# 12_-WIFI_Module_WF60.net
KiCad netlist of a schematic drawn in Altium Designer
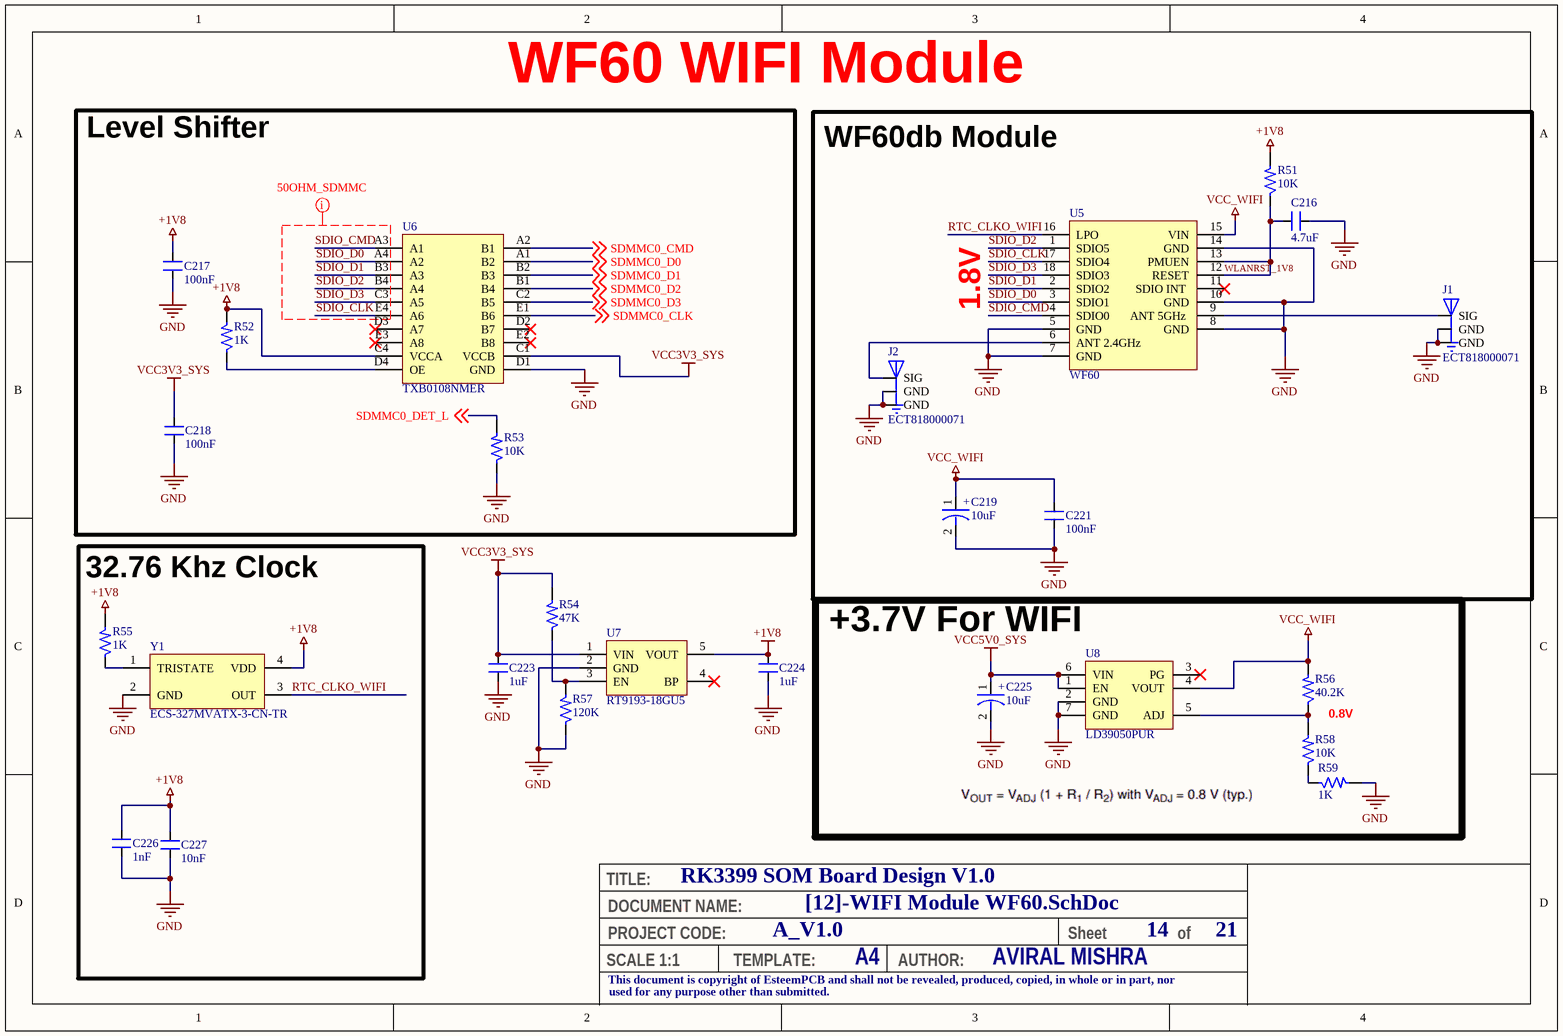
[diagram p0: [12]-WIFI Module WF60.SchDoc]

(export (version "E")
  (design (tool "Eeschema 10.0.6"))
  (components
    (comp (ref "C216")
      (value "4.7uF")
      (footprint "CAP_0402")
      (description "4.7µF ±10% 10V Ceramic Capacitor X5R 0402 (1005 Metric)")
      (fields
        (field (name "MANUFACTURER") "Samsung Electro-Mechanics")
        (field (name "MANUFACTURER PART NUMBER") "CL05A475KP5NRNC")
      )
      (libsource (lib "RK3399 _Module_Intlib") (part "CAP_4.7uF-10V-10%-0402"))
    )
    (comp (ref "C217")
      (value "100nF")
      (footprint "CAP_0402")
      (description "0.1µF ±10% 25V Ceramic Capacitor X7R 0402 (1005 Metric)")
      (fields
        (field (name "MANUFACTURER") "Walsin Technology Corporation")
        (field (name "MANUFACTURER PART NUMBER") "0402B104K250CT")
      )
      (libsource (lib "RK3399 _Module_Intlib") (part "CAP_100nF-25V-10%-0402"))
    )
    (comp (ref "C218")
      (value "100nF")
      (footprint "CAP_0402")
      (description "0.1µF ±10% 25V Ceramic Capacitor X7R 0402 (1005 Metric)")
      (fields
        (field (name "MANUFACTURER") "Walsin Technology Corporation")
        (field (name "MANUFACTURER PART NUMBER") "0402B104K250CT")
      )
      (libsource (lib "RK3399 _Module_Intlib") (part "CAP_100nF-25V-10%-0402"))
    )
    (comp (ref "C219")
      (value "10uF")
      (footprint "CAP-T_1206")
      (description "10µF Molded Tantalum Capacitors 16V 1206 (3216 Metric) 3Ohm")
      (fields
        (field (name "MANUFACTURER") "AVX Corporation")
        (field (name "MANUFACTURER PART NUMBER") "TAJA106K016SNJ")
      )
      (libsource (lib "RK3399 _Module_Intlib") (part "CAP-P_10uF-16V-10%-1206"))
    )
    (comp (ref "C221")
      (value "100nF")
      (footprint "CAP_0402")
      (description "0.1µF ±10% 25V Ceramic Capacitor X7R 0402 (1005 Metric)")
      (fields
        (field (name "MANUFACTURER") "Walsin Technology Corporation")
        (field (name "MANUFACTURER PART NUMBER") "0402B104K250CT")
      )
      (libsource (lib "RK3399 _Module_Intlib") (part "CAP_100nF-25V-10%-0402"))
    )
    (comp (ref "C223")
      (value "1uF")
      (footprint "CAP_0402")
      (description "1µF ±10% 16V Ceramic Capacitor X5R 0402 (1005 Metric)")
      (fields
        (field (name "MANUFACTURER") "Knowles Novacap")
        (field (name "MANUFACTURER PART NUMBER") "0402BW105K160YT")
      )
      (libsource (lib "RK3399 _Module_Schlib") (part "CAP_1uF-16V-10%-0402"))
    )
    (comp (ref "C224")
      (value "1uF")
      (footprint "CAP_0402")
      (description "1µF ±10% 16V Ceramic Capacitor X5R 0402 (1005 Metric)")
      (fields
        (field (name "MANUFACTURER") "Knowles Novacap")
        (field (name "MANUFACTURER PART NUMBER") "0402BW105K160YT")
      )
      (libsource (lib "RK3399 _Module_Schlib") (part "CAP_1uF-16V-10%-0402"))
    )
    (comp (ref "C225")
      (value "10uF")
      (footprint "CAP-T_1206")
      (description "10µF Molded Tantalum Capacitors 16V 1206 (3216 Metric) 3Ohm")
      (fields
        (field (name "MANUFACTURER") "AVX Corporation")
        (field (name "MANUFACTURER PART NUMBER") "TAJA106K016SNJ")
      )
      (libsource (lib "RK3399 _Module_Intlib") (part "CAP-P_10uF-16V-10%-1206"))
    )
    (comp (ref "C226")
      (value "1nF")
      (footprint "CAP_0402")
      (description "1000pF ±10% 16V Ceramic Capacitor X7R 0402 (1005 Metric)")
      (fields
        (field (name "MANUFACTURER") "Yageo")
        (field (name "MANUFACTURER PART NUMBER") "CC0402KRX7R7BB102")
      )
      (libsource (lib "RK3399 _Module_Intlib") (part "CAP_1nF-16V-10%-0402"))
    )
    (comp (ref "C227")
      (value "10nF")
      (footprint "CAP_0402")
      (description "10000pF ±10% 10V Ceramic Capacitor X7R 0402 (1005 Metric)")
      (fields
        (field (name "MANUFACTURER") "AVX Corporation")
        (field (name "MANUFACTURER PART NUMBER") "0402ZC103KAT2A")
      )
      (libsource (lib "RK3399 _Module_Intlib") (part "CAP_10nF-10V-10%-0402"))
    )
    (comp (ref "J1")
      (value "ECT818000071")
      (footprint "CON3_UFL_116_SMD_ST")
      (description "SMD RF Connectors/Coaxial Connectors RoHS")
      (fields (field (name "MANUFACTURER") "ECT"))
      (libsource (lib "RK3399 _Module_Intlib") (part "CON-PLG_3X1-ECT818000071-ST-SMD"))
    )
    (comp (ref "J2")
      (value "ECT818000071")
      (footprint "CON3_UFL_116_SMD_ST")
      (description "SMD RF Connectors/Coaxial Connectors RoHS")
      (fields (field (name "MANUFACTURER") "ECT"))
      (libsource (lib "RK3399 _Module_Intlib") (part "CON-PLG_3X1-ECT818000071-ST-SMD"))
    )
    (comp (ref "R51")
      (value "10K")
      (footprint "RES_0402")
      (description "10 kOhms ±1% 0.1W, 1/10W Chip Resistor 0402 (1005 Metric) Anti-Sulfur Thin Film")
      (fields
        (field (name "MANUFACTURER") "Vishay Beyschlag/Draloric/BC Components")
        (field (name "MANUFACTURER PART NUMBER") "MCS04020C1002FE000")
      )
      (libsource (lib "RK3399 _Module_Intlib") (part "RES_10K-0.1W-1%-0402"))
    )
    (comp (ref "R52")
      (value "1K")
      (footprint "RES_0402")
      (description "1 kOhms ±1% 0.1W, 1/10W Chip Resistor 0402 (1005 Metric) Anti-Sulfur Thin Film")
      (fields
        (field (name "MANUFACTURER") "Vishay Beyschlag/Draloric/BC Components")
        (field (name "MANUFACTURER PART NUMBER") "MCS04020C1001FE000")
      )
      (libsource (lib "RK3399 _Module_Intlib") (part "RES_1K-0.1W-1%-0402"))
    )
    (comp (ref "R53")
      (value "10K")
      (footprint "RES_0402")
      (description "10 kOhms ±1% 0.1W, 1/10W Chip Resistor 0402 (1005 Metric) Anti-Sulfur Thin Film")
      (fields
        (field (name "MANUFACTURER") "Vishay Beyschlag/Draloric/BC Components")
        (field (name "MANUFACTURER PART NUMBER") "MCS04020C1002FE000")
      )
      (libsource (lib "RK3399 _Module_Intlib") (part "RES_10K-0.1W-1%-0402"))
    )
    (comp (ref "R54")
      (value "47K")
      (footprint "RES_0402")
      (description "47 kOhms ±1% 0.1W, 1/10W Chip Resistor 0402 (1005 Metric) Automotive AEC-Q200 Thick Film")
      (fields
        (field (name "MANUFACTURER") "Panasonic Electronic Components")
        (field (name "MANUFACTURER PART NUMBER") "ERJ-2RKF4702X")
      )
      (libsource (lib "RK3399 _Module_Schlib") (part "RES_47K-0.1W-1%-0402"))
    )
    (comp (ref "R55")
      (value "1K")
      (footprint "RES_0402")
      (description "1 kOhms ±1% 0.1W, 1/10W Chip Resistor 0402 (1005 Metric) Anti-Sulfur Thin Film")
      (fields
        (field (name "MANUFACTURER") "Vishay Beyschlag/Draloric/BC Components")
        (field (name "MANUFACTURER PART NUMBER") "MCS04020C1001FE000")
      )
      (libsource (lib "RK3399 _Module_Intlib") (part "RES_1K-0.1W-1%-0402"))
    )
    (comp (ref "R56")
      (value "40.2K")
      (footprint "RES_0805")
      (description "40.2 kOhms ±1% 0.125W, 1/8W Chip Resistor 0805 (2012 Metric) Automotive AEC-Q200 Thick Film")
      (fields
        (field (name "MANUFACTURER") "TE Connectivity")
        (field (name "MANUFACTURER PART NUMBER") "RMCF0805FT40K2")
      )
      (libsource (lib "RK3399 _Module_Intlib") (part "RES_40.2K-0.125W-1%-0805"))
    )
    (comp (ref "R57")
      (value "120K")
      (footprint "RES_0402")
      (description "120 kOhms ±1% 0.1W, 1/10W Chip Resistor 0402 (1005 Metric) Anti-Sulfur Thin Film")
      (fields
        (field (name "MANUFACTURER") "Vishay Beyschlag/Draloric/BC Components")
        (field (name "MANUFACTURER PART NUMBER") "MCS04020C1203FE000")
      )
      (libsource (lib "RK3399 _Module_Schlib") (part "RES_120K-0.1W-1%-0402"))
    )
    (comp (ref "R58")
      (value "10K")
      (footprint "RES_0402")
      (description "10 kOhms ±1% 0.1W, 1/10W Chip Resistor 0402 (1005 Metric) Anti-Sulfur Thin Film")
      (fields
        (field (name "MANUFACTURER") "Vishay Beyschlag/Draloric/BC Components")
        (field (name "MANUFACTURER PART NUMBER") "MCS04020C1002FE000")
      )
      (libsource (lib "RK3399 _Module_Intlib") (part "RES_10K-0.1W-1%-0402"))
    )
    (comp (ref "R59")
      (value "1K")
      (footprint "RES_0402")
      (description "1 kOhms ±1% 0.1W, 1/10W Chip Resistor 0402 (1005 Metric) Anti-Sulfur Thin Film")
      (fields
        (field (name "MANUFACTURER") "Vishay Beyschlag/Draloric/BC Components")
        (field (name "MANUFACTURER PART NUMBER") "MCS04020C1001FE000")
      )
      (libsource (lib "RK3399 _Module_Intlib") (part "RES_1K-0.1W-1%-0402"))
    )
    (comp (ref "U5")
      (value "WF60")
      (footprint "MOD_WF60")
      (description "Amp’ed RF Tech presents the WF60 WiFi dual\r\nband module: 802.11abgn.")
      (fields (field (name "MANUFACTURER") "Amp’ed") (field (name "NYMBLE PART NUMBER") "1EA-AA-0568"))
      (libsource (lib "RK3399 _Module_Intlib") (part "MOD_WF60-SMD"))
    )
    (comp (ref "U6")
      (value "TXB0108NMER")
      (footprint "NFBGA_31.4_125.9X102.36")
      (fields (field (name "MANUFACTURER") "Texas Instruments"))
      (libsource (lib "RK3399 _Module_Intlib") (part "IC_TXB0108NMER"))
    )
    (comp (ref "U7")
      (value "RT9193-18GU5")
      (footprint "SC70-5")
      (description "Linear Voltage Regulator IC 1 Output 300mA SC-70-5")
      (fields (field (name "MANUFACTURER") "Richtek USA Inc."))
      (libsource (lib "RK3399 _Module_Schlib") (part "REG_1.8V-300mA-5.5V-SC70-5"))
    )
    (comp (ref "U8")
      (value "LD39050PUR")
      (footprint "DFN-6_37.4_165_33X15_SMD")
      (description "Adjustable 5.5V 0.8V 500mA DFN-6 Linear Voltage Regulators RoHS")
      (fields
        (field (name "MANUFACTURER") "STMicroelectronics")
        (field (name "NYMBLE PART NUMBER") "1EA-AA-0572")
      )
      (libsource (lib "RK3399 _Module_Intlib") (part "REG_5.5V-0~5.1V-0.5A-2.55W-DFN-6"))
    )
    (comp (ref "Y1")
      (value "ECS-327MVATX-3-CN-TR")
      (footprint "XTAL_57_35X31_SMD")
      (description "32.768kHz XO (Standard) CMOS Oscillator 1.6V ~ 3.6V Enable/Disable 4-SMD, No Lead")
      (fields (field (name "MANUFACTURER") "ECS INC") (field (name "NYMBLE PART NUMBER") "1EA-AA-0561"))
      (libsource (lib "RK3399 _Module_Intlib") (part "XTAL_ECS-327MVATX-2-CN-TR"))
    )
  )
  (nets
    (net (code "1") (name "+1V8") (class "Default")
      (node (ref "C217") (pin "2") (pinfunction "2_2") (pintype "passive"))
      (node (ref "C224") (pin "2") (pinfunction "2_2") (pintype "passive"))
      (node (ref "C226") (pin "2") (pinfunction "2_2") (pintype "passive"))
      (node (ref "C227") (pin "2") (pinfunction "2_2") (pintype "passive"))
      (node (ref "R51") (pin "2") (pinfunction "2_2") (pintype "passive"))
      (node (ref "R52") (pin "2") (pinfunction "2_2") (pintype "passive"))
      (node (ref "R55") (pin "2") (pinfunction "2_2") (pintype "passive"))
      (node (ref "U6") (pin "C4") (pinfunction "VCCA_C4") (pintype "passive"))
      (node (ref "U7") (pin "5") (pinfunction "VOUT_5") (pintype "passive"))
      (node (ref "Y1") (pin "4") (pinfunction "VDD_4") (pintype "passive"))
    )
    (net (code "2") (name "/RTC_CLKO_WIFI") (class "Default")
      (node (ref "U5") (pin "16") (pinfunction "LPO_16") (pintype "passive"))
      (node (ref "Y1") (pin "3") (pinfunction "OUT_3") (pintype "passive"))
    )
    (net (code "3") (name "/SDIO_CLK") (class "Default")
      (node (ref "U5") (pin "17") (pinfunction "SDIO4_17") (pintype "passive"))
      (node (ref "U6") (pin "E4") (pinfunction "A6_E4") (pintype "passive"))
    )
    (net (code "4") (name "/SDIO_CMD") (class "Default")
      (node (ref "U5") (pin "4") (pinfunction "SDIO0_4") (pintype "passive"))
      (node (ref "U6") (pin "A3") (pinfunction "A1_A3") (pintype "passive"))
    )
    (net (code "5") (name "/SDIO_D0") (class "Default")
      (node (ref "U5") (pin "3") (pinfunction "SDIO1_3") (pintype "passive"))
      (node (ref "U6") (pin "A4") (pinfunction "A2_A4") (pintype "passive"))
    )
    (net (code "6") (name "/SDIO_D1") (class "Default")
      (node (ref "U5") (pin "2") (pinfunction "SDIO2_2") (pintype "passive"))
      (node (ref "U6") (pin "B3") (pinfunction "A3_B3") (pintype "passive"))
    )
    (net (code "7") (name "/SDIO_D2") (class "Default")
      (node (ref "U5") (pin "1") (pinfunction "SDIO5_1") (pintype "passive"))
      (node (ref "U6") (pin "B4") (pinfunction "A4_B4") (pintype "passive"))
    )
    (net (code "8") (name "/SDIO_D3") (class "Default")
      (node (ref "U5") (pin "18") (pinfunction "SDIO3_18") (pintype "passive"))
      (node (ref "U6") (pin "C3") (pinfunction "A5_C3") (pintype "passive"))
    )
    (net (code "9") (name "/WLANRST_1V8") (class "Default")
      (node (ref "C216") (pin "2") (pinfunction "2_2") (pintype "passive"))
      (node (ref "R51") (pin "1") (pinfunction "1_1") (pintype "passive"))
      (node (ref "U5") (pin "12") (pinfunction "RESET_12") (pintype "passive"))
      (node (ref "U5") (pin "13") (pinfunction "PMUEN_13") (pintype "passive"))
    )
    (net (code "10") (name "GND") (class "Default")
      (node (ref "C216") (pin "1") (pinfunction "1_1") (pintype "passive"))
      (node (ref "C217") (pin "1") (pinfunction "1_1") (pintype "passive"))
      (node (ref "C218") (pin "1") (pinfunction "1_1") (pintype "passive"))
      (node (ref "C219") (pin "2") (pinfunction "2_2") (pintype "passive"))
      (node (ref "C221") (pin "1") (pinfunction "1_1") (pintype "passive"))
      (node (ref "C223") (pin "1") (pinfunction "1_1") (pintype "passive"))
      (node (ref "C224") (pin "1") (pinfunction "1_1") (pintype "passive"))
      (node (ref "C225") (pin "2") (pinfunction "2_2") (pintype "passive"))
      (node (ref "C226") (pin "1") (pinfunction "1_1") (pintype "passive"))
      (node (ref "C227") (pin "1") (pinfunction "1_1") (pintype "passive"))
      (node (ref "J1") (pin "1") (pinfunction "GND_1") (pintype "passive"))
      (node (ref "J1") (pin "3") (pinfunction "GND_3") (pintype "passive"))
      (node (ref "J2") (pin "1") (pinfunction "GND_1") (pintype "passive"))
      (node (ref "J2") (pin "3") (pinfunction "GND_3") (pintype "passive"))
      (node (ref "R53") (pin "1") (pinfunction "1_1") (pintype "passive"))
      (node (ref "R57") (pin "1") (pinfunction "1_1") (pintype "passive"))
      (node (ref "R59") (pin "2") (pinfunction "2_2") (pintype "passive"))
      (node (ref "U5") (pin "10") (pinfunction "GND_10") (pintype "passive"))
      (node (ref "U5") (pin "14") (pinfunction "GND_14") (pintype "passive"))
      (node (ref "U5") (pin "5") (pinfunction "GND_5") (pintype "passive"))
      (node (ref "U5") (pin "7") (pinfunction "GND_7") (pintype "passive"))
      (node (ref "U5") (pin "8") (pinfunction "GND_8") (pintype "passive"))
      (node (ref "U6") (pin "D1") (pinfunction "GND_D1") (pintype "passive"))
      (node (ref "U7") (pin "2") (pinfunction "GND_2") (pintype "passive"))
      (node (ref "U8") (pin "2") (pinfunction "GND_2") (pintype "passive"))
      (node (ref "U8") (pin "7") (pinfunction "GND_7") (pintype "passive"))
      (node (ref "Y1") (pin "2") (pinfunction "GND_2") (pintype "passive"))
    )
    (net (code "11") (name "Net-(J1-SIG)") (class "Default")
      (node (ref "J1") (pin "2") (pinfunction "SIG_2") (pintype "passive"))
      (node (ref "U5") (pin "9") (pinfunction "ANT_5GHz_9") (pintype "passive"))
    )
    (net (code "12") (name "Net-(J2-SIG)") (class "Default")
      (node (ref "J2") (pin "2") (pinfunction "SIG_2") (pintype "passive"))
      (node (ref "U5") (pin "6") (pinfunction "ANT_2.4GHz_6") (pintype "passive"))
    )
    (net (code "13") (name "Net-(R58-Pad1)") (class "Default")
      (node (ref "R58") (pin "1") (pinfunction "1_1") (pintype "passive"))
      (node (ref "R59") (pin "1") (pinfunction "1_1") (pintype "passive"))
    )
    (net (code "14") (name "Net-(U6-OE)") (class "Default")
      (node (ref "R52") (pin "1") (pinfunction "1_1") (pintype "passive"))
      (node (ref "U6") (pin "D4") (pinfunction "OE_D4") (pintype "passive"))
    )
    (net (code "15") (name "Net-(U7-EN)") (class "Default")
      (node (ref "R54") (pin "1") (pinfunction "1_1") (pintype "passive"))
      (node (ref "R57") (pin "2") (pinfunction "2_2") (pintype "passive"))
      (node (ref "U7") (pin "3") (pinfunction "EN_3") (pintype "passive"))
    )
    (net (code "16") (name "Net-(U8-ADJ)") (class "Default")
      (node (ref "R56") (pin "1") (pinfunction "1_1") (pintype "passive"))
      (node (ref "R58") (pin "2") (pinfunction "2_2") (pintype "passive"))
      (node (ref "U8") (pin "5") (pinfunction "ADJ_5") (pintype "passive"))
    )
    (net (code "17") (name "Net-(Y1-TRISTATE)") (class "Default")
      (node (ref "R55") (pin "1") (pinfunction "1_1") (pintype "passive"))
      (node (ref "Y1") (pin "1") (pinfunction "TRISTATE_1") (pintype "passive"))
    )
    (net (code "18") (name "SDMMC0_CLK") (class "Default")
      (node (ref "U6") (pin "E1") (pinfunction "B6_E1") (pintype "passive"))
    )
    (net (code "19") (name "SDMMC0_CMD") (class "Default")
      (node (ref "U6") (pin "A2") (pinfunction "B1_A2") (pintype "passive"))
    )
    (net (code "20") (name "SDMMC0_D0") (class "Default")
      (node (ref "U6") (pin "A1") (pinfunction "B2_A1") (pintype "passive"))
    )
    (net (code "21") (name "SDMMC0_D1") (class "Default")
      (node (ref "U6") (pin "B2") (pinfunction "B3_B2") (pintype "passive"))
    )
    (net (code "22") (name "SDMMC0_D2") (class "Default")
      (node (ref "U6") (pin "B1") (pinfunction "B4_B1") (pintype "passive"))
    )
    (net (code "23") (name "SDMMC0_D3") (class "Default")
      (node (ref "U6") (pin "C2") (pinfunction "B5_C2") (pintype "passive"))
    )
    (net (code "24") (name "SDMMC0_DET_L") (class "Default")
      (node (ref "R53") (pin "2") (pinfunction "2_2") (pintype "passive"))
    )
    (net (code "25") (name "VCC3V3_SYS") (class "Default")
      (node (ref "C218") (pin "2") (pinfunction "2_2") (pintype "passive"))
      (node (ref "C223") (pin "2") (pinfunction "2_2") (pintype "passive"))
      (node (ref "R54") (pin "2") (pinfunction "2_2") (pintype "passive"))
      (node (ref "U6") (pin "C1") (pinfunction "VCCB_C1") (pintype "passive"))
      (node (ref "U7") (pin "1") (pinfunction "VIN_1") (pintype "passive"))
    )
    (net (code "26") (name "VCC5V0_SYS") (class "Default")
      (node (ref "C225") (pin "1") (pinfunction "1_1") (pintype "passive"))
      (node (ref "U8") (pin "1") (pinfunction "EN_1") (pintype "passive"))
      (node (ref "U8") (pin "6") (pinfunction "VIN_6") (pintype "passive"))
    )
    (net (code "27") (name "VCC_WIFI") (class "Default")
      (node (ref "C219") (pin "1") (pinfunction "1_1") (pintype "passive"))
      (node (ref "C221") (pin "2") (pinfunction "2_2") (pintype "passive"))
      (node (ref "R56") (pin "2") (pinfunction "2_2") (pintype "passive"))
      (node (ref "U5") (pin "15") (pinfunction "VIN_15") (pintype "passive"))
      (node (ref "U8") (pin "4") (pinfunction "VOUT_4") (pintype "passive"))
    )
    (net (code "28") (name "unconnected-(U5-SDIO_INT-Pad11)") (class "Default")
      (node (ref "U5") (pin "11") (pinfunction "SDIO_INT_11") (pintype "passive+no_connect"))
    )
    (net (code "29") (name "unconnected-(U6-A7-PadD3)") (class "Default")
      (node (ref "U6") (pin "D3") (pinfunction "A7_D3") (pintype "passive+no_connect"))
    )
    (net (code "30") (name "unconnected-(U6-A8-PadE3)") (class "Default")
      (node (ref "U6") (pin "E3") (pinfunction "A8_E3") (pintype "passive+no_connect"))
    )
    (net (code "31") (name "unconnected-(U6-B7-PadD2)") (class "Default")
      (node (ref "U6") (pin "D2") (pinfunction "B7_D2") (pintype "passive+no_connect"))
    )
    (net (code "32") (name "unconnected-(U6-B8-PadE2)") (class "Default")
      (node (ref "U6") (pin "E2") (pinfunction "B8_E2") (pintype "passive+no_connect"))
    )
    (net (code "33") (name "unconnected-(U7-BP-Pad4)") (class "Default")
      (node (ref "U7") (pin "4") (pinfunction "BP_4") (pintype "passive+no_connect"))
    )
    (net (code "34") (name "unconnected-(U8-PG-Pad3)") (class "Default")
      (node (ref "U8") (pin "3") (pinfunction "PG_3") (pintype "passive+no_connect"))
    )
  )
)
